# Sheet1.net
KiCad netlist of a schematic drawn in Altium Designer
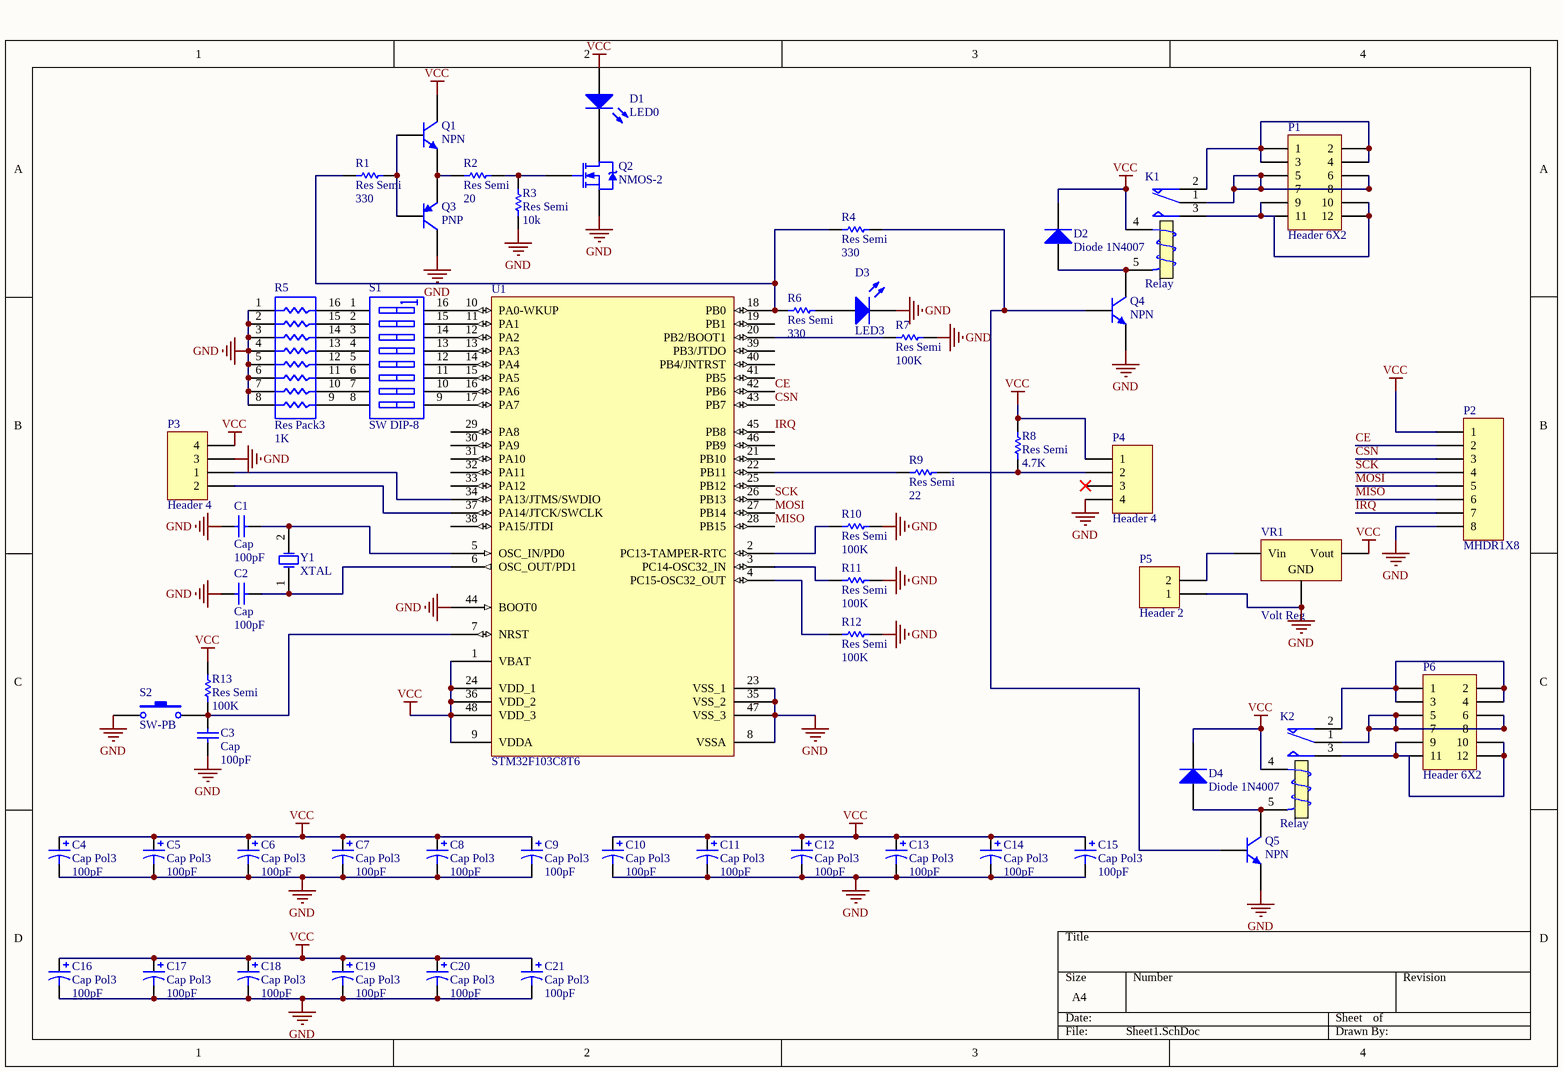
[diagram p0: Sheet1.SchDoc]

(export (version "E")
  (design (tool "Eeschema 10.0.6"))
  (components
    (comp (ref "C1")
      (value "Cap")
      (footprint "0402")
      (description "Capacitor")
      (fields (field (name "ALTIUM_VALUE") "100pF") (field (name "PUBLISHER") "Altium Limited"))
      (libsource (lib "Miscellaneous Devices") (part "Cap"))
    )
    (comp (ref "C2")
      (value "Cap")
      (footprint "0402")
      (description "Capacitor")
      (fields (field (name "ALTIUM_VALUE") "100pF") (field (name "PUBLISHER") "Altium Limited"))
      (libsource (lib "Miscellaneous Devices") (part "Cap"))
    )
    (comp (ref "C3")
      (value "Cap")
      (footprint "0402")
      (description "Capacitor")
      (fields (field (name "ALTIUM_VALUE") "100pF") (field (name "PUBLISHER") "Altium Limited"))
      (libsource (lib "Miscellaneous Devices") (part "Cap"))
    )
    (comp (ref "C4")
      (value "Cap Pol3")
      (footprint "0402")
      (description "Polarized Capacitor (Surface Mount)")
      (fields (field (name "ALTIUM_VALUE") "100pF") (field (name "PUBLISHER") "Altium Limited"))
      (libsource (lib "Miscellaneous Devices") (part "Cap Pol3"))
    )
    (comp (ref "C5")
      (value "Cap Pol3")
      (footprint "0402")
      (description "Polarized Capacitor (Surface Mount)")
      (fields (field (name "ALTIUM_VALUE") "100pF") (field (name "PUBLISHER") "Altium Limited"))
      (libsource (lib "Miscellaneous Devices") (part "Cap Pol3"))
    )
    (comp (ref "C6")
      (value "Cap Pol3")
      (footprint "0402")
      (description "Polarized Capacitor (Surface Mount)")
      (fields (field (name "ALTIUM_VALUE") "100pF") (field (name "PUBLISHER") "Altium Limited"))
      (libsource (lib "Miscellaneous Devices") (part "Cap Pol3"))
    )
    (comp (ref "C7")
      (value "Cap Pol3")
      (footprint "0402")
      (description "Polarized Capacitor (Surface Mount)")
      (fields (field (name "ALTIUM_VALUE") "100pF") (field (name "PUBLISHER") "Altium Limited"))
      (libsource (lib "Miscellaneous Devices") (part "Cap Pol3"))
    )
    (comp (ref "C8")
      (value "Cap Pol3")
      (footprint "0402")
      (description "Polarized Capacitor (Surface Mount)")
      (fields (field (name "ALTIUM_VALUE") "100pF") (field (name "PUBLISHER") "Altium Limited"))
      (libsource (lib "Miscellaneous Devices") (part "Cap Pol3"))
    )
    (comp (ref "C9")
      (value "Cap Pol3")
      (footprint "0402")
      (description "Polarized Capacitor (Surface Mount)")
      (fields (field (name "ALTIUM_VALUE") "100pF") (field (name "PUBLISHER") "Altium Limited"))
      (libsource (lib "Miscellaneous Devices") (part "Cap Pol3"))
    )
    (comp (ref "C10")
      (value "Cap Pol3")
      (footprint "0402")
      (description "Polarized Capacitor (Surface Mount)")
      (fields (field (name "ALTIUM_VALUE") "100pF") (field (name "PUBLISHER") "Altium Limited"))
      (libsource (lib "Miscellaneous Devices") (part "Cap Pol3"))
    )
    (comp (ref "C11")
      (value "Cap Pol3")
      (footprint "0402")
      (description "Polarized Capacitor (Surface Mount)")
      (fields (field (name "ALTIUM_VALUE") "100pF") (field (name "PUBLISHER") "Altium Limited"))
      (libsource (lib "Miscellaneous Devices") (part "Cap Pol3"))
    )
    (comp (ref "C12")
      (value "Cap Pol3")
      (footprint "0402")
      (description "Polarized Capacitor (Surface Mount)")
      (fields (field (name "ALTIUM_VALUE") "100pF") (field (name "PUBLISHER") "Altium Limited"))
      (libsource (lib "Miscellaneous Devices") (part "Cap Pol3"))
    )
    (comp (ref "C13")
      (value "Cap Pol3")
      (footprint "0402")
      (description "Polarized Capacitor (Surface Mount)")
      (fields (field (name "ALTIUM_VALUE") "100pF") (field (name "PUBLISHER") "Altium Limited"))
      (libsource (lib "Miscellaneous Devices") (part "Cap Pol3"))
    )
    (comp (ref "C14")
      (value "Cap Pol3")
      (footprint "0402")
      (description "Polarized Capacitor (Surface Mount)")
      (fields (field (name "ALTIUM_VALUE") "100pF") (field (name "PUBLISHER") "Altium Limited"))
      (libsource (lib "Miscellaneous Devices") (part "Cap Pol3"))
    )
    (comp (ref "C15")
      (value "Cap Pol3")
      (footprint "0402")
      (description "Polarized Capacitor (Surface Mount)")
      (fields (field (name "ALTIUM_VALUE") "100pF") (field (name "PUBLISHER") "Altium Limited"))
      (libsource (lib "Miscellaneous Devices") (part "Cap Pol3"))
    )
    (comp (ref "C16")
      (value "Cap Pol3")
      (footprint "1005[0402]")
      (description "Polarized Capacitor (Surface Mount)")
      (fields (field (name "ALTIUM_VALUE") "100pF") (field (name "PUBLISHER") "Altium Limited"))
      (libsource (lib "Miscellaneous Devices") (part "Cap Pol3"))
    )
    (comp (ref "C17")
      (value "Cap Pol3")
      (footprint "1005[0402]")
      (description "Polarized Capacitor (Surface Mount)")
      (fields (field (name "ALTIUM_VALUE") "100pF") (field (name "PUBLISHER") "Altium Limited"))
      (libsource (lib "Miscellaneous Devices") (part "Cap Pol3"))
    )
    (comp (ref "C18")
      (value "Cap Pol3")
      (footprint "0402")
      (description "Polarized Capacitor (Surface Mount)")
      (fields (field (name "ALTIUM_VALUE") "100pF") (field (name "PUBLISHER") "Altium Limited"))
      (libsource (lib "Miscellaneous Devices") (part "Cap Pol3"))
    )
    (comp (ref "C19")
      (value "Cap Pol3")
      (footprint "0402")
      (description "Polarized Capacitor (Surface Mount)")
      (fields (field (name "ALTIUM_VALUE") "100pF") (field (name "PUBLISHER") "Altium Limited"))
      (libsource (lib "Miscellaneous Devices") (part "Cap Pol3"))
    )
    (comp (ref "C20")
      (value "Cap Pol3")
      (footprint "0402")
      (description "Polarized Capacitor (Surface Mount)")
      (fields (field (name "ALTIUM_VALUE") "100pF") (field (name "PUBLISHER") "Altium Limited"))
      (libsource (lib "Miscellaneous Devices") (part "Cap Pol3"))
    )
    (comp (ref "C21")
      (value "Cap Pol3")
      (footprint "0402")
      (description "Polarized Capacitor (Surface Mount)")
      (fields (field (name "ALTIUM_VALUE") "100pF") (field (name "PUBLISHER") "Altium Limited"))
      (libsource (lib "Miscellaneous Devices") (part "Cap Pol3"))
    )
    (comp (ref "D1")
      (value "LED0")
      (footprint "HA-C1")
      (description "Typical INFRARED GaAs LED")
      (fields (field (name "PUBLISHER") "Altium Limited"))
      (libsource (lib "Miscellaneous Devices") (part "LED0"))
    )
    (comp (ref "D2")
      (value "Diode 1N4007")
      (footprint "DO-41")
      (description "1 Amp General Purpose Rectifier")
      (fields (field (name "PUBLISHER") "Altium Limited"))
      (libsource (lib "Miscellaneous Devices") (part "Diode 1N4007"))
    )
    (comp (ref "D3")
      (value "LED3")
      (footprint "3.5X2.8X1.9")
      (description "Typical BLUE SiC LED")
      (fields (field (name "PUBLISHER") "Altium Limited"))
      (libsource (lib "Miscellaneous Devices") (part "LED3"))
    )
    (comp (ref "D4")
      (value "Diode 1N4007")
      (footprint "DO-41")
      (description "1 Amp General Purpose Rectifier")
      (fields (field (name "PUBLISHER") "Altium Limited"))
      (libsource (lib "Miscellaneous Devices") (part "Diode 1N4007"))
    )
    (comp (ref "K1")
      (value "Relay")
      (footprint "MODULE5B")
      (description "SPDT Relay")
      (fields (field (name "PUBLISHER") "Altium Limited"))
      (libsource (lib "Miscellaneous Devices") (part "Relay"))
    )
    (comp (ref "K2")
      (value "Relay")
      (footprint "MODULE5B")
      (description "SPDT Relay")
      (fields (field (name "PUBLISHER") "Altium Limited"))
      (libsource (lib "Miscellaneous Devices") (part "Relay"))
    )
    (comp (ref "P1")
      (value "Header 6X2")
      (footprint "HDR2X6")
      (description "Header, 6-Pin, Dual row")
      (fields (field (name "PUBLISHER") "Altium Limited"))
      (libsource (lib "Miscellaneous Connectors") (part "Header 6X2"))
    )
    (comp (ref "P2")
      (value "MHDR1X8")
      (footprint "MHDR1X8")
      (description "Header, 8-Pin")
      (fields (field (name "PUBLISHER") "Altium Limited"))
      (libsource (lib "Miscellaneous Connectors") (part "MHDR1X8"))
    )
    (comp (ref "P3")
      (value "Header 4")
      (footprint "HDR1X4")
      (description "Header, 4-Pin")
      (fields (field (name "PUBLISHER") "Altium Limited"))
      (libsource (lib "Miscellaneous Connectors") (part "Header 4"))
    )
    (comp (ref "P4")
      (value "Header 4")
      (footprint "HDR1X4")
      (description "Header, 4-Pin")
      (fields (field (name "PUBLISHER") "Altium Limited"))
      (libsource (lib "") (part "Header 4_1"))
    )
    (comp (ref "P5")
      (value "Header 2")
      (footprint "HDR1X2")
      (description "Header, 2-Pin")
      (fields (field (name "PUBLISHER") "Altium Limited"))
      (libsource (lib "Miscellaneous Connectors") (part "Header 2"))
    )
    (comp (ref "P6")
      (value "Header 6X2")
      (footprint "HDR2X6")
      (description "Header, 6-Pin, Dual row")
      (fields (field (name "PUBLISHER") "Altium Limited"))
      (libsource (lib "Miscellaneous Connectors") (part "Header 6X2"))
    )
    (comp (ref "Q1")
      (value "NPN")
      (footprint "TO-226")
      (description "NPN Bipolar Transistor")
      (fields (field (name "PUBLISHER") "Altium Limited"))
      (libsource (lib "Miscellaneous Devices") (part "NPN"))
    )
    (comp (ref "Q2")
      (value "NMOS-2")
      (footprint "TO-220AB")
      (description "N-Channel Power MOSFET")
      (fields (field (name "PUBLISHER") "Altium Limited"))
      (libsource (lib "Miscellaneous Devices") (part "NMOS-2"))
    )
    (comp (ref "Q3")
      (value "PNP")
      (footprint "SOT-23B")
      (description "PNP Bipolar Transistor")
      (fields (field (name "PUBLISHER") "Altium Limited"))
      (libsource (lib "Miscellaneous Devices") (part "PNP"))
    )
    (comp (ref "Q4")
      (value "NPN")
      (footprint "TO-226")
      (description "NPN Bipolar Transistor")
      (fields (field (name "PUBLISHER") "Altium Limited"))
      (libsource (lib "Miscellaneous Devices") (part "NPN"))
    )
    (comp (ref "Q5")
      (value "NPN")
      (footprint "TO-226")
      (description "NPN Bipolar Transistor")
      (fields (field (name "PUBLISHER") "Altium Limited"))
      (libsource (lib "Miscellaneous Devices") (part "NPN"))
    )
    (comp (ref "R1")
      (value "Res Semi")
      (footprint "2012[0805]")
      (description "Semiconductor Resistor")
      (fields (field (name "ALTIUM_VALUE") "330") (field (name "PUBLISHER") "Altium Limited"))
      (libsource (lib "Miscellaneous Devices") (part "Res Semi"))
    )
    (comp (ref "R2")
      (value "Res Semi")
      (footprint "2012[0805]")
      (description "Semiconductor Resistor")
      (fields (field (name "ALTIUM_VALUE") "20") (field (name "PUBLISHER") "Altium Limited"))
      (libsource (lib "Miscellaneous Devices") (part "Res Semi"))
    )
    (comp (ref "R3")
      (value "Res Semi")
      (footprint "2012[0805]")
      (description "Semiconductor Resistor")
      (fields (field (name "ALTIUM_VALUE") "10k") (field (name "PUBLISHER") "Altium Limited"))
      (libsource (lib "Miscellaneous Devices") (part "Res Semi"))
    )
    (comp (ref "R4")
      (value "Res Semi")
      (footprint "2012[0805]")
      (description "Semiconductor Resistor")
      (fields (field (name "ALTIUM_VALUE") "330") (field (name "PUBLISHER") "Altium Limited"))
      (libsource (lib "Miscellaneous Devices") (part "Res Semi"))
    )
    (comp (ref "R5")
      (value "Res Pack3")
      (footprint "EXB2HV")
      (description "Isolated Resistor Network")
      (fields (field (name "ALTIUM_VALUE") "1K") (field (name "PUBLISHER") "Altium Limited"))
      (libsource (lib "Miscellaneous Devices") (part "Res Pack3"))
    )
    (comp (ref "R6")
      (value "Res Semi")
      (footprint "0402")
      (description "Semiconductor Resistor")
      (fields (field (name "ALTIUM_VALUE") "330") (field (name "PUBLISHER") "Altium Limited"))
      (libsource (lib "Miscellaneous Devices") (part "Res Semi"))
    )
    (comp (ref "R7")
      (value "Res Semi")
      (footprint "0402")
      (description "Semiconductor Resistor")
      (fields (field (name "ALTIUM_VALUE") "100K") (field (name "PUBLISHER") "Altium Limited"))
      (libsource (lib "Miscellaneous Devices") (part "Res Semi"))
    )
    (comp (ref "R8")
      (value "Res Semi")
      (footprint "1005[0402]")
      (description "Semiconductor Resistor")
      (fields (field (name "ALTIUM_VALUE") "4.7K") (field (name "PUBLISHER") "Altium Limited"))
      (libsource (lib "Miscellaneous Devices") (part "Res Semi"))
    )
    (comp (ref "R9")
      (value "Res Semi")
      (footprint "0402")
      (description "Semiconductor Resistor")
      (fields (field (name "ALTIUM_VALUE") "22") (field (name "PUBLISHER") "Altium Limited"))
      (libsource (lib "Miscellaneous Devices") (part "Res Semi"))
    )
    (comp (ref "R10")
      (value "Res Semi")
      (footprint "0402")
      (description "Semiconductor Resistor")
      (fields (field (name "ALTIUM_VALUE") "100K") (field (name "PUBLISHER") "Altium Limited"))
      (libsource (lib "Miscellaneous Devices") (part "Res Semi"))
    )
    (comp (ref "R11")
      (value "Res Semi")
      (footprint "0402")
      (description "Semiconductor Resistor")
      (fields (field (name "ALTIUM_VALUE") "100K") (field (name "PUBLISHER") "Altium Limited"))
      (libsource (lib "Miscellaneous Devices") (part "Res Semi"))
    )
    (comp (ref "R12")
      (value "Res Semi")
      (footprint "0402")
      (description "Semiconductor Resistor")
      (fields (field (name "ALTIUM_VALUE") "100K") (field (name "PUBLISHER") "Altium Limited"))
      (libsource (lib "Miscellaneous Devices") (part "Res Semi"))
    )
    (comp (ref "R13")
      (value "Res Semi")
      (footprint "0402")
      (description "Semiconductor Resistor")
      (fields (field (name "ALTIUM_VALUE") "100K") (field (name "PUBLISHER") "Altium Limited"))
      (libsource (lib "Miscellaneous Devices") (part "Res Semi"))
    )
    (comp (ref "S1")
      (value "SW DIP-8")
      (footprint "DIP_SW_8WAY_SMD")
      (description "DIP Switch, 8 Position, SPST")
      (fields (field (name "PUBLISHER") "Altium Limited"))
      (libsource (lib "Miscellaneous Devices") (part "SW DIP-8"))
    )
    (comp (ref "S2")
      (value "SW-PB")
      (footprint "5025[2010]")
      (description "Switch")
      (fields (field (name "PUBLISHER") "Altium Limited"))
      (libsource (lib "Miscellaneous Devices") (part "SW-PB"))
    )
    (comp (ref "U1")
      (value "STM32F103C8T6")
      (footprint "LQFP48_L")
      (description "STM32 ARM-based 32-bit MCU with 64 Kbytes Flash, 48-pin LQFP, Industrial Temperature")
      (fields (field (name "PUBLISHER") "*"))
      (libsource (lib "*") (part "STM32F103C8T6"))
    )
    (comp (ref "VR1")
      (value "Volt Reg")
      (footprint "SOT89")
      (description "Voltage Regulator")
      (fields (field (name "PUBLISHER") "Altium Limited"))
      (libsource (lib "Miscellaneous Devices") (part "Volt Reg"))
    )
    (comp (ref "Y1")
      (value "XTAL")
      (footprint "3225[1210]")
      (description "Crystal Oscillator")
      (fields (field (name "PUBLISHER") "Altium Limited"))
      (libsource (lib "Miscellaneous Devices") (part "XTAL"))
    )
  )
  (nets
    (net (code "1") (name "/CE") (class "Default")
      (node (ref "P2") (pin "2") (pinfunction "2_2") (pintype "passive"))
      (node (ref "U1") (pin "42") (pinfunction "PB6_42") (pintype "bidirectional"))
    )
    (net (code "2") (name "/CSN") (class "Default")
      (node (ref "P2") (pin "3") (pinfunction "3_3") (pintype "passive"))
      (node (ref "U1") (pin "43") (pinfunction "PB7_43") (pintype "bidirectional"))
    )
    (net (code "3") (name "/IRQ") (class "Default")
      (node (ref "P2") (pin "7") (pinfunction "7_7") (pintype "passive"))
      (node (ref "U1") (pin "45") (pinfunction "PB8_45") (pintype "bidirectional"))
    )
    (net (code "4") (name "/MISO") (class "Default")
      (node (ref "P2") (pin "6") (pinfunction "6_6") (pintype "passive"))
      (node (ref "U1") (pin "28") (pinfunction "PB15_28") (pintype "bidirectional"))
    )
    (net (code "5") (name "/MOSI") (class "Default")
      (node (ref "P2") (pin "5") (pinfunction "5_5") (pintype "passive"))
      (node (ref "U1") (pin "27") (pinfunction "PB14_27") (pintype "bidirectional"))
    )
    (net (code "6") (name "/SCK") (class "Default")
      (node (ref "P2") (pin "4") (pinfunction "4_4") (pintype "passive"))
      (node (ref "U1") (pin "26") (pinfunction "PB13_26") (pintype "bidirectional"))
    )
    (net (code "7") (name "GND") (class "Default")
      (node (ref "C1") (pin "1") (pinfunction "1_1") (pintype "passive"))
      (node (ref "C10") (pin "2") (pinfunction "2_2") (pintype "passive"))
      (node (ref "C11") (pin "2") (pinfunction "2_2") (pintype "passive"))
      (node (ref "C12") (pin "2") (pinfunction "2_2") (pintype "passive"))
      (node (ref "C13") (pin "2") (pinfunction "2_2") (pintype "passive"))
      (node (ref "C14") (pin "2") (pinfunction "2_2") (pintype "passive"))
      (node (ref "C15") (pin "2") (pinfunction "2_2") (pintype "passive"))
      (node (ref "C16") (pin "2") (pinfunction "2_2") (pintype "passive"))
      (node (ref "C17") (pin "2") (pinfunction "2_2") (pintype "passive"))
      (node (ref "C18") (pin "2") (pinfunction "2_2") (pintype "passive"))
      (node (ref "C19") (pin "2") (pinfunction "2_2") (pintype "passive"))
      (node (ref "C2") (pin "1") (pinfunction "1_1") (pintype "passive"))
      (node (ref "C20") (pin "2") (pinfunction "2_2") (pintype "passive"))
      (node (ref "C21") (pin "2") (pinfunction "2_2") (pintype "passive"))
      (node (ref "C3") (pin "1") (pinfunction "1_1") (pintype "passive"))
      (node (ref "C4") (pin "2") (pinfunction "2_2") (pintype "passive"))
      (node (ref "C5") (pin "2") (pinfunction "2_2") (pintype "passive"))
      (node (ref "C6") (pin "2") (pinfunction "2_2") (pintype "passive"))
      (node (ref "C7") (pin "2") (pinfunction "2_2") (pintype "passive"))
      (node (ref "C8") (pin "2") (pinfunction "2_2") (pintype "passive"))
      (node (ref "C9") (pin "2") (pinfunction "2_2") (pintype "passive"))
      (node (ref "D3") (pin "2") (pinfunction "K_2") (pintype "passive"))
      (node (ref "P2") (pin "8") (pinfunction "8_8") (pintype "passive"))
      (node (ref "P3") (pin "3") (pinfunction "3_3") (pintype "passive"))
      (node (ref "P4") (pin "4") (pinfunction "4_4") (pintype "passive"))
      (node (ref "P5") (pin "1") (pinfunction "1_1") (pintype "passive"))
      (node (ref "Q2") (pin "3") (pinfunction "S_3") (pintype "passive"))
      (node (ref "Q3") (pin "1") (pinfunction "C_1") (pintype "passive"))
      (node (ref "Q4") (pin "3") (pinfunction "E_3") (pintype "passive"))
      (node (ref "Q5") (pin "3") (pinfunction "E_3") (pintype "passive"))
      (node (ref "R10") (pin "1") (pinfunction "1_1") (pintype "passive"))
      (node (ref "R11") (pin "1") (pinfunction "1_1") (pintype "passive"))
      (node (ref "R12") (pin "1") (pinfunction "1_1") (pintype "passive"))
      (node (ref "R3") (pin "1") (pinfunction "1_1") (pintype "passive"))
      (node (ref "R5") (pin "1") (pinfunction "1_1") (pintype "passive"))
      (node (ref "R5") (pin "2") (pinfunction "2_2") (pintype "passive"))
      (node (ref "R5") (pin "3") (pinfunction "3_3") (pintype "passive"))
      (node (ref "R5") (pin "4") (pinfunction "4_4") (pintype "passive"))
      (node (ref "R5") (pin "5") (pinfunction "5_5") (pintype "passive"))
      (node (ref "R5") (pin "6") (pinfunction "6_6") (pintype "passive"))
      (node (ref "R5") (pin "7") (pinfunction "7_7") (pintype "passive"))
      (node (ref "R5") (pin "8") (pinfunction "8_8") (pintype "passive"))
      (node (ref "R7") (pin "2") (pinfunction "2_2") (pintype "passive"))
      (node (ref "S2") (pin "1") (pinfunction "1_1") (pintype "passive"))
      (node (ref "U1") (pin "23") (pinfunction "VSS_1_23") (pintype "power_in"))
      (node (ref "U1") (pin "35") (pinfunction "VSS_2_35") (pintype "power_in"))
      (node (ref "U1") (pin "44") (pinfunction "BOOT0_44") (pintype "input"))
      (node (ref "U1") (pin "47") (pinfunction "VSS_3_47") (pintype "power_in"))
      (node (ref "U1") (pin "8") (pinfunction "VSSA_8") (pintype "power_in"))
      (node (ref "VR1") (pin "2") (pinfunction "GND_2") (pintype "passive"))
    )
    (net (code "8") (name "Net-(D1-K)") (class "Default")
      (node (ref "D1") (pin "2") (pinfunction "K_2") (pintype "passive"))
      (node (ref "Q2") (pin "2") (pinfunction "D_2") (pintype "passive"))
    )
    (net (code "9") (name "Net-(D2-A)") (class "Default")
      (node (ref "D2") (pin "1") (pinfunction "A_1") (pintype "passive"))
      (node (ref "K1") (pin "5") (pinfunction "T2_5") (pintype "passive"))
      (node (ref "Q4") (pin "1") (pinfunction "C_1") (pintype "passive"))
    )
    (net (code "10") (name "Net-(D3-A)") (class "Default")
      (node (ref "D3") (pin "1") (pinfunction "A_1") (pintype "passive"))
      (node (ref "R6") (pin "2") (pinfunction "2_2") (pintype "passive"))
    )
    (net (code "11") (name "Net-(D4-A)") (class "Default")
      (node (ref "D4") (pin "1") (pinfunction "A_1") (pintype "passive"))
      (node (ref "K2") (pin "5") (pinfunction "T2_5") (pintype "passive"))
      (node (ref "Q5") (pin "1") (pinfunction "C_1") (pintype "passive"))
    )
    (net (code "12") (name "Net-(K1-COM)") (class "Default")
      (node (ref "K1") (pin "1") (pinfunction "COM_1") (pintype "passive"))
      (node (ref "P1") (pin "5") (pinfunction "5_5") (pintype "passive"))
      (node (ref "P1") (pin "6") (pinfunction "6_6") (pintype "passive"))
      (node (ref "P1") (pin "7") (pinfunction "7_7") (pintype "passive"))
      (node (ref "P1") (pin "8") (pinfunction "8_8") (pintype "passive"))
    )
    (net (code "13") (name "Net-(K1-NC)") (class "Default")
      (node (ref "K1") (pin "2") (pinfunction "NC_2") (pintype "passive"))
      (node (ref "P1") (pin "1") (pinfunction "1_1") (pintype "passive"))
      (node (ref "P1") (pin "2") (pinfunction "2_2") (pintype "passive"))
      (node (ref "P1") (pin "3") (pinfunction "3_3") (pintype "passive"))
      (node (ref "P1") (pin "4") (pinfunction "4_4") (pintype "passive"))
    )
    (net (code "14") (name "Net-(K1-NO)") (class "Default")
      (node (ref "K1") (pin "3") (pinfunction "NO_3") (pintype "passive"))
      (node (ref "P1") (pin "10") (pinfunction "10_10") (pintype "passive"))
      (node (ref "P1") (pin "11") (pinfunction "11_11") (pintype "passive"))
      (node (ref "P1") (pin "12") (pinfunction "12_12") (pintype "passive"))
      (node (ref "P1") (pin "9") (pinfunction "9_9") (pintype "passive"))
    )
    (net (code "15") (name "Net-(K2-COM)") (class "Default")
      (node (ref "K2") (pin "1") (pinfunction "COM_1") (pintype "passive"))
      (node (ref "P6") (pin "5") (pinfunction "5_5") (pintype "passive"))
      (node (ref "P6") (pin "6") (pinfunction "6_6") (pintype "passive"))
      (node (ref "P6") (pin "7") (pinfunction "7_7") (pintype "passive"))
      (node (ref "P6") (pin "8") (pinfunction "8_8") (pintype "passive"))
    )
    (net (code "16") (name "Net-(K2-NC)") (class "Default")
      (node (ref "K2") (pin "2") (pinfunction "NC_2") (pintype "passive"))
      (node (ref "P6") (pin "1") (pinfunction "1_1") (pintype "passive"))
      (node (ref "P6") (pin "2") (pinfunction "2_2") (pintype "passive"))
      (node (ref "P6") (pin "3") (pinfunction "3_3") (pintype "passive"))
      (node (ref "P6") (pin "4") (pinfunction "4_4") (pintype "passive"))
    )
    (net (code "17") (name "Net-(K2-NO)") (class "Default")
      (node (ref "K2") (pin "3") (pinfunction "NO_3") (pintype "passive"))
      (node (ref "P6") (pin "10") (pinfunction "10_10") (pintype "passive"))
      (node (ref "P6") (pin "11") (pinfunction "11_11") (pintype "passive"))
      (node (ref "P6") (pin "12") (pinfunction "12_12") (pintype "passive"))
      (node (ref "P6") (pin "9") (pinfunction "9_9") (pintype "passive"))
    )
    (net (code "18") (name "Net-(P4-Pad2)") (class "Default")
      (node (ref "P4") (pin "2") (pinfunction "2_2") (pintype "passive"))
      (node (ref "R8") (pin "1") (pinfunction "1_1") (pintype "passive"))
      (node (ref "R9") (pin "2") (pinfunction "2_2") (pintype "passive"))
    )
    (net (code "19") (name "Net-(Q1-B)") (class "Default")
      (node (ref "Q1") (pin "2") (pinfunction "B_2") (pintype "passive"))
      (node (ref "Q3") (pin "2") (pinfunction "B_2") (pintype "passive"))
      (node (ref "R1") (pin "2") (pinfunction "2_2") (pintype "passive"))
    )
    (net (code "20") (name "Net-(Q1-E)") (class "Default")
      (node (ref "Q1") (pin "3") (pinfunction "E_3") (pintype "passive"))
      (node (ref "Q3") (pin "3") (pinfunction "E_3") (pintype "passive"))
      (node (ref "R2") (pin "1") (pinfunction "1_1") (pintype "passive"))
    )
    (net (code "21") (name "Net-(Q2-G)") (class "Default")
      (node (ref "Q2") (pin "1") (pinfunction "G_1") (pintype "passive"))
      (node (ref "R2") (pin "2") (pinfunction "2_2") (pintype "passive"))
      (node (ref "R3") (pin "2") (pinfunction "2_2") (pintype "passive"))
    )
    (net (code "22") (name "Net-(Q4-B)") (class "Default")
      (node (ref "Q4") (pin "2") (pinfunction "B_2") (pintype "passive"))
      (node (ref "Q5") (pin "2") (pinfunction "B_2") (pintype "passive"))
      (node (ref "R4") (pin "2") (pinfunction "2_2") (pintype "passive"))
    )
    (net (code "23") (name "Net-(S1-A1)") (class "Default")
      (node (ref "R5") (pin "16") (pinfunction "16_16") (pintype "passive"))
      (node (ref "S1") (pin "1") (pinfunction "A1_1") (pintype "passive"))
    )
    (net (code "24") (name "Net-(S1-A2)") (class "Default")
      (node (ref "R5") (pin "15") (pinfunction "15_15") (pintype "passive"))
      (node (ref "S1") (pin "2") (pinfunction "A2_2") (pintype "passive"))
    )
    (net (code "25") (name "Net-(S1-A3)") (class "Default")
      (node (ref "R5") (pin "14") (pinfunction "14_14") (pintype "passive"))
      (node (ref "S1") (pin "3") (pinfunction "A3_3") (pintype "passive"))
    )
    (net (code "26") (name "Net-(S1-A4)") (class "Default")
      (node (ref "R5") (pin "13") (pinfunction "13_13") (pintype "passive"))
      (node (ref "S1") (pin "4") (pinfunction "A4_4") (pintype "passive"))
    )
    (net (code "27") (name "Net-(S1-A5)") (class "Default")
      (node (ref "R5") (pin "12") (pinfunction "12_12") (pintype "passive"))
      (node (ref "S1") (pin "5") (pinfunction "A5_5") (pintype "passive"))
    )
    (net (code "28") (name "Net-(S1-A6)") (class "Default")
      (node (ref "R5") (pin "11") (pinfunction "11_11") (pintype "passive"))
      (node (ref "S1") (pin "6") (pinfunction "A6_6") (pintype "passive"))
    )
    (net (code "29") (name "Net-(S1-A7)") (class "Default")
      (node (ref "R5") (pin "10") (pinfunction "10_10") (pintype "passive"))
      (node (ref "S1") (pin "7") (pinfunction "A7_7") (pintype "passive"))
    )
    (net (code "30") (name "Net-(S1-A8)") (class "Default")
      (node (ref "R5") (pin "9") (pinfunction "9_9") (pintype "passive"))
      (node (ref "S1") (pin "8") (pinfunction "A8_8") (pintype "passive"))
    )
    (net (code "31") (name "Net-(S1-B1)") (class "Default")
      (node (ref "S1") (pin "16") (pinfunction "B1_16") (pintype "passive"))
      (node (ref "U1") (pin "10") (pinfunction "PA0-WKUP_10") (pintype "bidirectional"))
    )
    (net (code "32") (name "Net-(S1-B2)") (class "Default")
      (node (ref "S1") (pin "15") (pinfunction "B2_15") (pintype "passive"))
      (node (ref "U1") (pin "11") (pinfunction "PA1_11") (pintype "bidirectional"))
    )
    (net (code "33") (name "Net-(S1-B3)") (class "Default")
      (node (ref "S1") (pin "14") (pinfunction "B3_14") (pintype "passive"))
      (node (ref "U1") (pin "12") (pinfunction "PA2_12") (pintype "bidirectional"))
    )
    (net (code "34") (name "Net-(S1-B4)") (class "Default")
      (node (ref "S1") (pin "13") (pinfunction "B4_13") (pintype "passive"))
      (node (ref "U1") (pin "13") (pinfunction "PA3_13") (pintype "bidirectional"))
    )
    (net (code "35") (name "Net-(S1-B5)") (class "Default")
      (node (ref "S1") (pin "12") (pinfunction "B5_12") (pintype "passive"))
      (node (ref "U1") (pin "14") (pinfunction "PA4_14") (pintype "bidirectional"))
    )
    (net (code "36") (name "Net-(S1-B6)") (class "Default")
      (node (ref "S1") (pin "11") (pinfunction "B6_11") (pintype "passive"))
      (node (ref "U1") (pin "15") (pinfunction "PA5_15") (pintype "bidirectional"))
    )
    (net (code "37") (name "Net-(S1-B7)") (class "Default")
      (node (ref "S1") (pin "10") (pinfunction "B7_10") (pintype "passive"))
      (node (ref "U1") (pin "16") (pinfunction "PA6_16") (pintype "bidirectional"))
    )
    (net (code "38") (name "Net-(S1-B8)") (class "Default")
      (node (ref "S1") (pin "9") (pinfunction "B8_9") (pintype "passive"))
      (node (ref "U1") (pin "17") (pinfunction "PA7_17") (pintype "bidirectional"))
    )
    (net (code "39") (name "Net-(U1-NRST)") (class "Default")
      (node (ref "C3") (pin "2") (pinfunction "2_2") (pintype "passive"))
      (node (ref "R13") (pin "1") (pinfunction "1_1") (pintype "passive"))
      (node (ref "S2") (pin "2") (pinfunction "2_2") (pintype "passive"))
      (node (ref "U1") (pin "7") (pinfunction "NRST_7") (pintype "bidirectional"))
    )
    (net (code "40") (name "Net-(U1-OSC_IN{slash}PD0)") (class "Default")
      (node (ref "C1") (pin "2") (pinfunction "2_2") (pintype "passive"))
      (node (ref "U1") (pin "5") (pinfunction "OSC_IN/PD0_5") (pintype "input"))
      (node (ref "Y1") (pin "2") (pinfunction "OSC2_2") (pintype "passive"))
    )
    (net (code "41") (name "Net-(U1-OSC_OUT{slash}PD1)") (class "Default")
      (node (ref "C2") (pin "2") (pinfunction "2_2") (pintype "passive"))
      (node (ref "U1") (pin "6") (pinfunction "OSC_OUT/PD1_6") (pintype "output"))
      (node (ref "Y1") (pin "1") (pinfunction "OSC1_1") (pintype "passive"))
    )
    (net (code "42") (name "Net-(U1-PA13{slash}JTMS{slash}SWDIO)") (class "Default")
      (node (ref "P3") (pin "1") (pinfunction "1_1") (pintype "passive"))
      (node (ref "U1") (pin "34") (pinfunction "PA13/JTMS/SWDIO_34") (pintype "bidirectional"))
    )
    (net (code "43") (name "Net-(U1-PA14{slash}JTCK{slash}SWCLK)") (class "Default")
      (node (ref "P3") (pin "2") (pinfunction "2_2") (pintype "passive"))
      (node (ref "U1") (pin "37") (pinfunction "PA14/JTCK/SWCLK_37") (pintype "bidirectional"))
    )
    (net (code "44") (name "Net-(U1-PB0)") (class "Default")
      (node (ref "R1") (pin "1") (pinfunction "1_1") (pintype "passive"))
      (node (ref "R4") (pin "1") (pinfunction "1_1") (pintype "passive"))
      (node (ref "R6") (pin "1") (pinfunction "1_1") (pintype "passive"))
      (node (ref "U1") (pin "18") (pinfunction "PB0_18") (pintype "bidirectional"))
    )
    (net (code "45") (name "Net-(U1-PB2{slash}BOOT1)") (class "Default")
      (node (ref "R7") (pin "1") (pinfunction "1_1") (pintype "passive"))
      (node (ref "U1") (pin "20") (pinfunction "PB2/BOOT1_20") (pintype "bidirectional"))
    )
    (net (code "46") (name "Net-(U1-PB11)") (class "Default")
      (node (ref "R9") (pin "1") (pinfunction "1_1") (pintype "passive"))
      (node (ref "U1") (pin "22") (pinfunction "PB11_22") (pintype "bidirectional"))
    )
    (net (code "47") (name "Net-(U1-PC13-TAMPER-RTC)") (class "Default")
      (node (ref "R10") (pin "2") (pinfunction "2_2") (pintype "passive"))
      (node (ref "U1") (pin "2") (pinfunction "PC13-TAMPER-RTC_2") (pintype "bidirectional"))
    )
    (net (code "48") (name "Net-(U1-PC14-OSC32_IN)") (class "Default")
      (node (ref "R11") (pin "2") (pinfunction "2_2") (pintype "passive"))
      (node (ref "U1") (pin "3") (pinfunction "PC14-OSC32_IN_3") (pintype "bidirectional"))
    )
    (net (code "49") (name "Net-(U1-PC15-OSC32_OUT)") (class "Default")
      (node (ref "R12") (pin "2") (pinfunction "2_2") (pintype "passive"))
      (node (ref "U1") (pin "4") (pinfunction "PC15-OSC32_OUT_4") (pintype "bidirectional"))
    )
    (net (code "50") (name "Net-(VR1-Vin)") (class "Default")
      (node (ref "P5") (pin "2") (pinfunction "2_2") (pintype "passive"))
      (node (ref "VR1") (pin "1") (pinfunction "Vin_1") (pintype "passive"))
    )
    (net (code "51") (name "VCC") (class "Default")
      (node (ref "C10") (pin "1") (pinfunction "1_1") (pintype "passive"))
      (node (ref "C11") (pin "1") (pinfunction "1_1") (pintype "passive"))
      (node (ref "C12") (pin "1") (pinfunction "1_1") (pintype "passive"))
      (node (ref "C13") (pin "1") (pinfunction "1_1") (pintype "passive"))
      (node (ref "C14") (pin "1") (pinfunction "1_1") (pintype "passive"))
      (node (ref "C15") (pin "1") (pinfunction "1_1") (pintype "passive"))
      (node (ref "C16") (pin "1") (pinfunction "1_1") (pintype "passive"))
      (node (ref "C17") (pin "1") (pinfunction "1_1") (pintype "passive"))
      (node (ref "C18") (pin "1") (pinfunction "1_1") (pintype "passive"))
      (node (ref "C19") (pin "1") (pinfunction "1_1") (pintype "passive"))
      (node (ref "C20") (pin "1") (pinfunction "1_1") (pintype "passive"))
      (node (ref "C21") (pin "1") (pinfunction "1_1") (pintype "passive"))
      (node (ref "C4") (pin "1") (pinfunction "1_1") (pintype "passive"))
      (node (ref "C5") (pin "1") (pinfunction "1_1") (pintype "passive"))
      (node (ref "C6") (pin "1") (pinfunction "1_1") (pintype "passive"))
      (node (ref "C7") (pin "1") (pinfunction "1_1") (pintype "passive"))
      (node (ref "C8") (pin "1") (pinfunction "1_1") (pintype "passive"))
      (node (ref "C9") (pin "1") (pinfunction "1_1") (pintype "passive"))
      (node (ref "D1") (pin "1") (pinfunction "A_1") (pintype "passive"))
      (node (ref "D2") (pin "2") (pinfunction "K_2") (pintype "passive"))
      (node (ref "D4") (pin "2") (pinfunction "K_2") (pintype "passive"))
      (node (ref "K1") (pin "4") (pinfunction "T1_4") (pintype "passive"))
      (node (ref "K2") (pin "4") (pinfunction "T1_4") (pintype "passive"))
      (node (ref "P2") (pin "1") (pinfunction "1_1") (pintype "passive"))
      (node (ref "P3") (pin "4") (pinfunction "4_4") (pintype "passive"))
      (node (ref "P4") (pin "1") (pinfunction "1_1") (pintype "passive"))
      (node (ref "Q1") (pin "1") (pinfunction "C_1") (pintype "passive"))
      (node (ref "R13") (pin "2") (pinfunction "2_2") (pintype "passive"))
      (node (ref "R8") (pin "2") (pinfunction "2_2") (pintype "passive"))
      (node (ref "U1") (pin "1") (pinfunction "VBAT_1") (pintype "power_in"))
      (node (ref "U1") (pin "24") (pinfunction "VDD_1_24") (pintype "power_in"))
      (node (ref "U1") (pin "36") (pinfunction "VDD_2_36") (pintype "power_in"))
      (node (ref "U1") (pin "48") (pinfunction "VDD_3_48") (pintype "power_in"))
      (node (ref "U1") (pin "9") (pinfunction "VDDA_9") (pintype "power_in"))
      (node (ref "VR1") (pin "3") (pinfunction "Vout_3") (pintype "passive"))
    )
    (net (code "52") (name "unconnected-(P4-Pad3)") (class "Default")
      (node (ref "P4") (pin "3") (pinfunction "3_3") (pintype "passive+no_connect"))
    )
    (net (code "53") (name "unconnected-(U1-PA8-Pad29)") (class "Default")
      (node (ref "U1") (pin "29") (pinfunction "PA8_29") (pintype "bidirectional"))
    )
    (net (code "54") (name "unconnected-(U1-PA9-Pad30)") (class "Default")
      (node (ref "U1") (pin "30") (pinfunction "PA9_30") (pintype "bidirectional"))
    )
    (net (code "55") (name "unconnected-(U1-PA10-Pad31)") (class "Default")
      (node (ref "U1") (pin "31") (pinfunction "PA10_31") (pintype "bidirectional"))
    )
    (net (code "56") (name "unconnected-(U1-PA11-Pad32)") (class "Default")
      (node (ref "U1") (pin "32") (pinfunction "PA11_32") (pintype "bidirectional"))
    )
    (net (code "57") (name "unconnected-(U1-PA12-Pad33)") (class "Default")
      (node (ref "U1") (pin "33") (pinfunction "PA12_33") (pintype "bidirectional"))
    )
    (net (code "58") (name "unconnected-(U1-PA15{slash}JTDI-Pad38)") (class "Default")
      (node (ref "U1") (pin "38") (pinfunction "PA15/JTDI_38") (pintype "bidirectional"))
    )
    (net (code "59") (name "unconnected-(U1-PB1-Pad19)") (class "Default")
      (node (ref "U1") (pin "19") (pinfunction "PB1_19") (pintype "bidirectional"))
    )
    (net (code "60") (name "unconnected-(U1-PB3{slash}JTDO-Pad39)") (class "Default")
      (node (ref "U1") (pin "39") (pinfunction "PB3/JTDO_39") (pintype "bidirectional"))
    )
    (net (code "61") (name "unconnected-(U1-PB4{slash}JNTRST-Pad40)") (class "Default")
      (node (ref "U1") (pin "40") (pinfunction "PB4/JNTRST_40") (pintype "bidirectional"))
    )
    (net (code "62") (name "unconnected-(U1-PB5-Pad41)") (class "Default")
      (node (ref "U1") (pin "41") (pinfunction "PB5_41") (pintype "bidirectional"))
    )
    (net (code "63") (name "unconnected-(U1-PB9-Pad46)") (class "Default")
      (node (ref "U1") (pin "46") (pinfunction "PB9_46") (pintype "bidirectional"))
    )
    (net (code "64") (name "unconnected-(U1-PB10-Pad21)") (class "Default")
      (node (ref "U1") (pin "21") (pinfunction "PB10_21") (pintype "bidirectional"))
    )
    (net (code "65") (name "unconnected-(U1-PB12-Pad25)") (class "Default")
      (node (ref "U1") (pin "25") (pinfunction "PB12_25") (pintype "bidirectional"))
    )
  )
)
